# R121.net
KiCad netlist of a schematic drawn in EAGLE
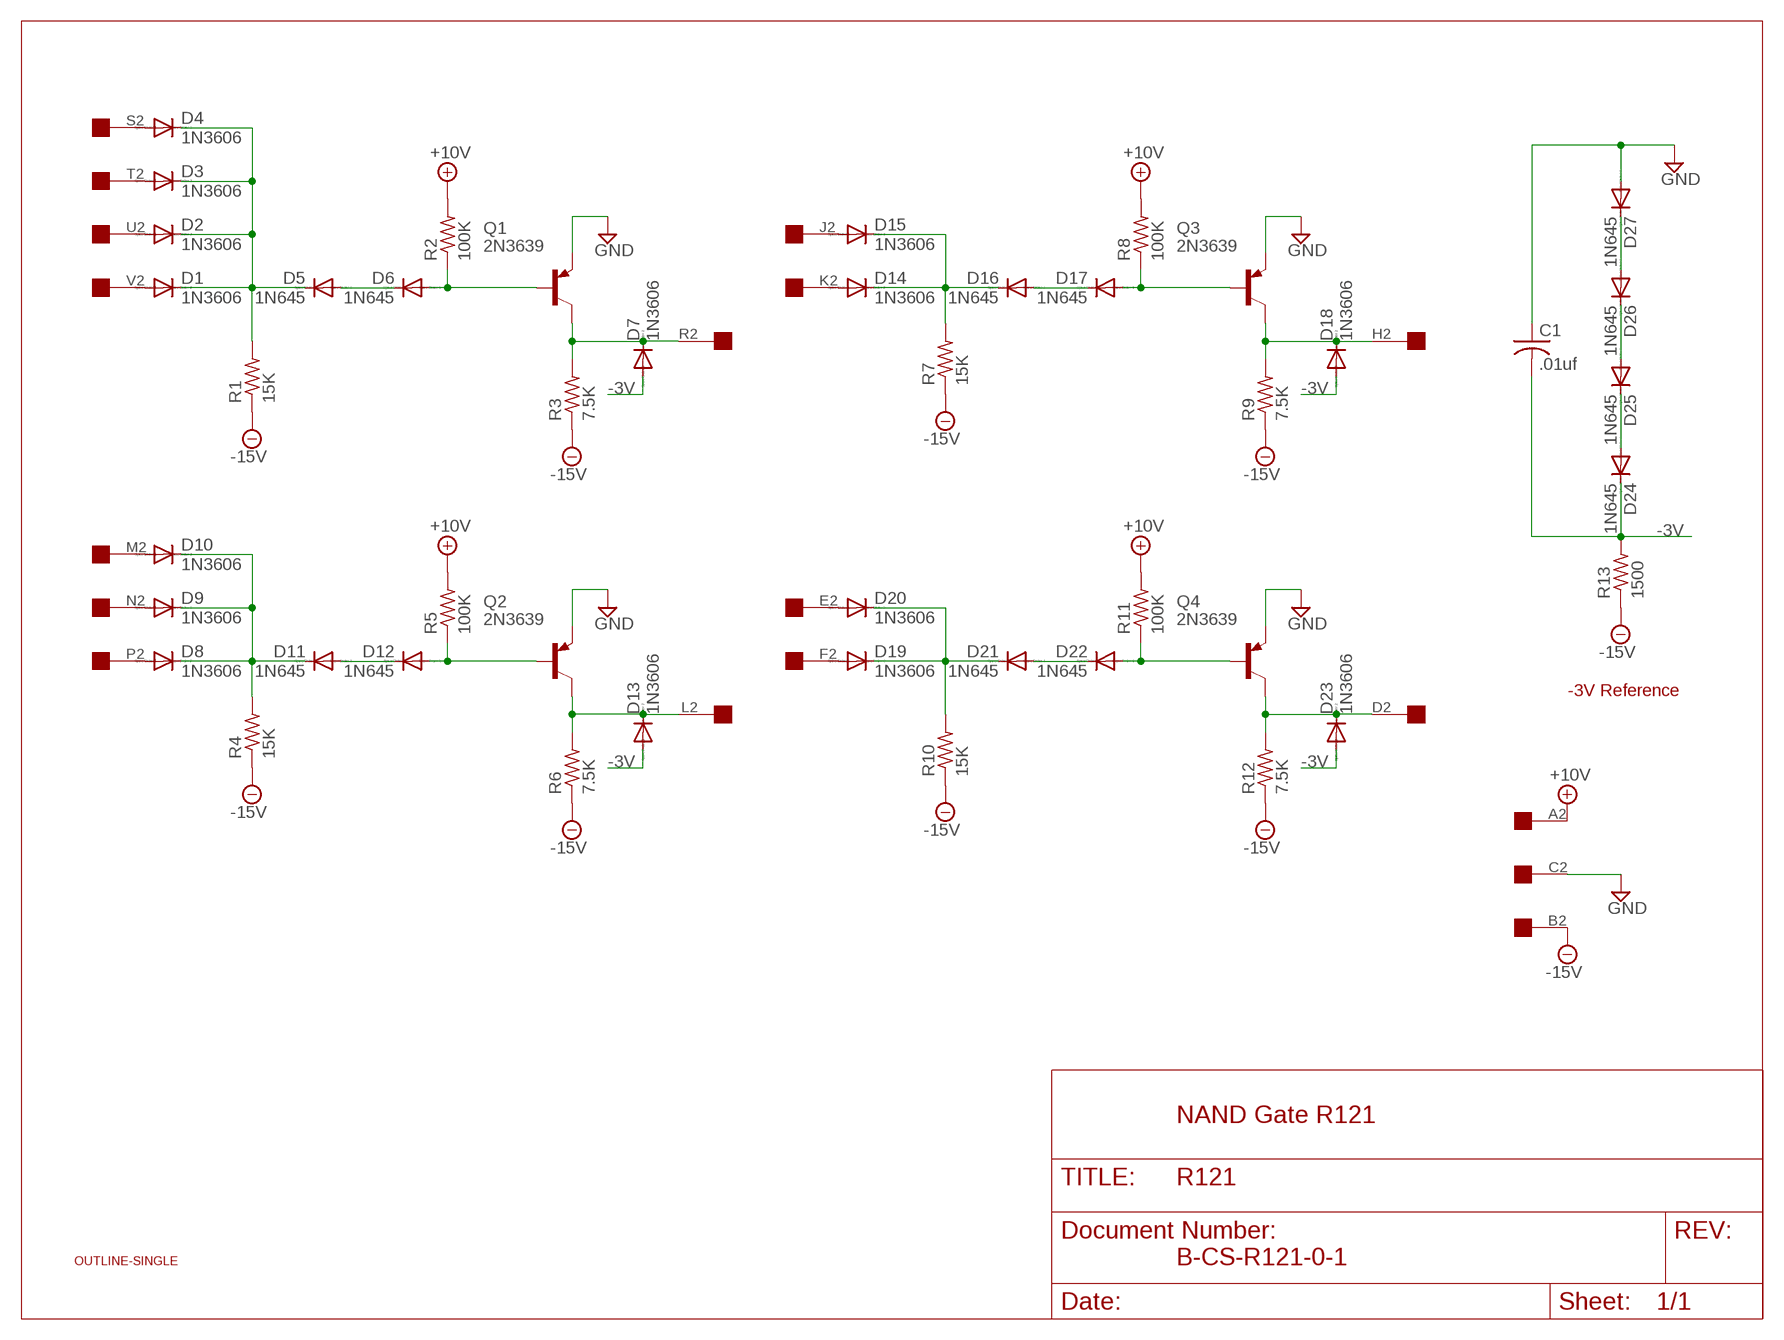
[diagram p0: schematic, sheet 1]

(export (version "E")
  (design (tool "Eeschema 10.0.6"))
  (components
    (comp (ref "C1")
      (value ".01uf")
      (footprint "eagle-import:C050-025X075")
      (libsource (lib "eagle-import") (part "C-US050-025X075"))
    )
    (comp (ref "D1")
      (value "1N3606")
      (footprint "eagle-import:DO35-10")
      (libsource (lib "eagle-import") (part "1N4148DO35-10"))
    )
    (comp (ref "D2")
      (value "1N3606")
      (footprint "eagle-import:DO35-10")
      (libsource (lib "eagle-import") (part "1N4148DO35-10"))
    )
    (comp (ref "D3")
      (value "1N3606")
      (footprint "eagle-import:DO35-10")
      (libsource (lib "eagle-import") (part "1N4148DO35-10"))
    )
    (comp (ref "D4")
      (value "1N3606")
      (footprint "eagle-import:DO35-10")
      (libsource (lib "eagle-import") (part "1N4148DO35-10"))
    )
    (comp (ref "D5")
      (value "1N645")
      (footprint "eagle-import:DO35-10")
      (libsource (lib "eagle-import") (part "1N4148DO35-10"))
    )
    (comp (ref "D6")
      (value "1N645")
      (footprint "eagle-import:DO35-10")
      (libsource (lib "eagle-import") (part "1N4148DO35-10"))
    )
    (comp (ref "D7")
      (value "1N3606")
      (footprint "eagle-import:DO35-10")
      (libsource (lib "eagle-import") (part "1N4148DO35-10"))
    )
    (comp (ref "D8")
      (value "1N3606")
      (footprint "eagle-import:DO35-10")
      (libsource (lib "eagle-import") (part "1N4148DO35-10"))
    )
    (comp (ref "D9")
      (value "1N3606")
      (footprint "eagle-import:DO35-10")
      (libsource (lib "eagle-import") (part "1N4148DO35-10"))
    )
    (comp (ref "D10")
      (value "1N3606")
      (footprint "eagle-import:DO35-10")
      (libsource (lib "eagle-import") (part "1N4148DO35-10"))
    )
    (comp (ref "D11")
      (value "1N645")
      (footprint "eagle-import:DO35-10")
      (libsource (lib "eagle-import") (part "1N4148DO35-10"))
    )
    (comp (ref "D12")
      (value "1N645")
      (footprint "eagle-import:DO35-10")
      (libsource (lib "eagle-import") (part "1N4148DO35-10"))
    )
    (comp (ref "D13")
      (value "1N3606")
      (footprint "eagle-import:DO35-10")
      (libsource (lib "eagle-import") (part "1N4148DO35-10"))
    )
    (comp (ref "D14")
      (value "1N3606")
      (footprint "eagle-import:DO35-10")
      (libsource (lib "eagle-import") (part "1N4148DO35-10"))
    )
    (comp (ref "D15")
      (value "1N3606")
      (footprint "eagle-import:DO35-10")
      (libsource (lib "eagle-import") (part "1N4148DO35-10"))
    )
    (comp (ref "D16")
      (value "1N645")
      (footprint "eagle-import:DO35-10")
      (libsource (lib "eagle-import") (part "1N4148DO35-10"))
    )
    (comp (ref "D17")
      (value "1N645")
      (footprint "eagle-import:DO35-10")
      (libsource (lib "eagle-import") (part "1N4148DO35-10"))
    )
    (comp (ref "D18")
      (value "1N3606")
      (footprint "eagle-import:DO35-10")
      (libsource (lib "eagle-import") (part "1N4148DO35-10"))
    )
    (comp (ref "D19")
      (value "1N3606")
      (footprint "eagle-import:DO35-10")
      (libsource (lib "eagle-import") (part "1N4148DO35-10"))
    )
    (comp (ref "D20")
      (value "1N3606")
      (footprint "eagle-import:DO35-10")
      (libsource (lib "eagle-import") (part "1N4148DO35-10"))
    )
    (comp (ref "D21")
      (value "1N645")
      (footprint "eagle-import:DO35-10")
      (libsource (lib "eagle-import") (part "1N4148DO35-10"))
    )
    (comp (ref "D22")
      (value "1N645")
      (footprint "eagle-import:DO35-10")
      (libsource (lib "eagle-import") (part "1N4148DO35-10"))
    )
    (comp (ref "D23")
      (value "1N3606")
      (footprint "eagle-import:DO35-10")
      (libsource (lib "eagle-import") (part "1N4148DO35-10"))
    )
    (comp (ref "D24")
      (value "1N645")
      (footprint "eagle-import:DO35-10")
      (libsource (lib "eagle-import") (part "1N4148DO35-10"))
    )
    (comp (ref "D25")
      (value "1N645")
      (footprint "eagle-import:DO35-10")
      (libsource (lib "eagle-import") (part "1N4148DO35-10"))
    )
    (comp (ref "D26")
      (value "1N645")
      (footprint "eagle-import:DO35-10")
      (libsource (lib "eagle-import") (part "1N4148DO35-10"))
    )
    (comp (ref "D27")
      (value "1N645")
      (footprint "eagle-import:DO35-10")
      (libsource (lib "eagle-import") (part "1N4148DO35-10"))
    )
    (comp (ref "Q1")
      (value "2N3639")
      (footprint "eagle-import:TO39")
      (libsource (lib "eagle-import") (part "2N3637"))
    )
    (comp (ref "Q2")
      (value "2N3639")
      (footprint "eagle-import:TO39")
      (libsource (lib "eagle-import") (part "2N3637"))
    )
    (comp (ref "Q3")
      (value "2N3639")
      (footprint "eagle-import:TO39")
      (libsource (lib "eagle-import") (part "2N3637"))
    )
    (comp (ref "Q4")
      (value "2N3639")
      (footprint "eagle-import:TO39")
      (libsource (lib "eagle-import") (part "2N3637"))
    )
    (comp (ref "R1")
      (value "15K")
      (footprint "eagle-import:0207_10")
      (libsource (lib "eagle-import") (part "R-US_0207/10"))
    )
    (comp (ref "R2")
      (value "100K")
      (footprint "eagle-import:0207_10")
      (libsource (lib "eagle-import") (part "R-US_0207/10"))
    )
    (comp (ref "R3")
      (value "7.5K")
      (footprint "eagle-import:0207_10")
      (libsource (lib "eagle-import") (part "R-US_0207/10"))
    )
    (comp (ref "R4")
      (value "15K")
      (footprint "eagle-import:0207_10")
      (libsource (lib "eagle-import") (part "R-US_0207/10"))
    )
    (comp (ref "R5")
      (value "100K")
      (footprint "eagle-import:0207_10")
      (libsource (lib "eagle-import") (part "R-US_0207/10"))
    )
    (comp (ref "R6")
      (value "7.5K")
      (footprint "eagle-import:0207_10")
      (libsource (lib "eagle-import") (part "R-US_0207/10"))
    )
    (comp (ref "R7")
      (value "15K")
      (footprint "eagle-import:0207_10")
      (libsource (lib "eagle-import") (part "R-US_0207/10"))
    )
    (comp (ref "R8")
      (value "100K")
      (footprint "eagle-import:0207_10")
      (libsource (lib "eagle-import") (part "R-US_0207/10"))
    )
    (comp (ref "R9")
      (value "7.5K")
      (footprint "eagle-import:0207_10")
      (libsource (lib "eagle-import") (part "R-US_0207/10"))
    )
    (comp (ref "R10")
      (value "15K")
      (footprint "eagle-import:0207_10")
      (libsource (lib "eagle-import") (part "R-US_0207/10"))
    )
    (comp (ref "R11")
      (value "100K")
      (footprint "eagle-import:0207_10")
      (libsource (lib "eagle-import") (part "R-US_0207/10"))
    )
    (comp (ref "R12")
      (value "7.5K")
      (footprint "eagle-import:0207_10")
      (libsource (lib "eagle-import") (part "R-US_0207/10"))
    )
    (comp (ref "R13")
      (value "1500")
      (footprint "eagle-import:0207_10")
      (libsource (lib "eagle-import") (part "R-US_0207/10"))
    )
    (comp (ref "U$1")
      (value "OUTLINE-SINGLE")
      (footprint "eagle-import:SINGLE")
      (libsource (lib "eagle-import") (part "OUTLINE-SINGLE"))
    )
    (comp (ref "U$2")
      (value "EDGE-1")
      (footprint "eagle-import:EDGE-CON1")
      (libsource (lib "eagle-import") (part "EDGE-1"))
    )
  )
  (nets
    (net (code "1") (name "+10V") (class "Default")
      (node (ref "R11") (pin "2") (pinfunction "2_2") (pintype "passive"))
      (node (ref "R2") (pin "2") (pinfunction "2_2") (pintype "passive"))
      (node (ref "R5") (pin "2") (pinfunction "2_2") (pintype "passive"))
      (node (ref "R8") (pin "2") (pinfunction "2_2") (pintype "passive"))
      (node (ref "U$2") (pin "A2") (pinfunction "1_A2") (pintype "bidirectional"))
    )
    (net (code "2") (name "-15V") (class "Default")
      (node (ref "R1") (pin "1") (pinfunction "1_1") (pintype "passive"))
      (node (ref "R10") (pin "1") (pinfunction "1_1") (pintype "passive"))
      (node (ref "R12") (pin "1") (pinfunction "1_1") (pintype "passive"))
      (node (ref "R13") (pin "1") (pinfunction "1_1") (pintype "passive"))
      (node (ref "R3") (pin "1") (pinfunction "1_1") (pintype "passive"))
      (node (ref "R4") (pin "1") (pinfunction "1_1") (pintype "passive"))
      (node (ref "R6") (pin "1") (pinfunction "1_1") (pintype "passive"))
      (node (ref "R7") (pin "1") (pinfunction "1_1") (pintype "passive"))
      (node (ref "R9") (pin "1") (pinfunction "1_1") (pintype "passive"))
      (node (ref "U$2") (pin "B2") (pinfunction "1_B2") (pintype "bidirectional"))
    )
    (net (code "3") (name "/-3V") (class "Default")
      (node (ref "C1") (pin "2") (pinfunction "2_2") (pintype "passive"))
      (node (ref "D13") (pin "A") (pinfunction "A_A") (pintype "passive"))
      (node (ref "D18") (pin "A") (pinfunction "A_A") (pintype "passive"))
      (node (ref "D23") (pin "A") (pinfunction "A_A") (pintype "passive"))
      (node (ref "D24") (pin "C") (pinfunction "C_C") (pintype "passive"))
      (node (ref "D7") (pin "A") (pinfunction "A_A") (pintype "passive"))
      (node (ref "R13") (pin "2") (pinfunction "2_2") (pintype "passive"))
    )
    (net (code "4") (name "GND") (class "Default")
      (node (ref "C1") (pin "1") (pinfunction "1_1") (pintype "passive"))
      (node (ref "D27") (pin "A") (pinfunction "A_A") (pintype "passive"))
      (node (ref "Q1") (pin "1") (pinfunction "E_1") (pintype "passive"))
      (node (ref "Q2") (pin "1") (pinfunction "E_1") (pintype "passive"))
      (node (ref "Q3") (pin "1") (pinfunction "E_1") (pintype "passive"))
      (node (ref "Q4") (pin "1") (pinfunction "E_1") (pintype "passive"))
      (node (ref "U$2") (pin "C2") (pinfunction "1_C2") (pintype "bidirectional"))
    )
    (net (code "5") (name "Net-(D1-PadC)") (class "Default")
      (node (ref "D1") (pin "C") (pinfunction "C_C") (pintype "passive"))
      (node (ref "D2") (pin "C") (pinfunction "C_C") (pintype "passive"))
      (node (ref "D3") (pin "C") (pinfunction "C_C") (pintype "passive"))
      (node (ref "D4") (pin "C") (pinfunction "C_C") (pintype "passive"))
      (node (ref "D5") (pin "C") (pinfunction "C_C") (pintype "passive"))
      (node (ref "R1") (pin "2") (pinfunction "2_2") (pintype "passive"))
    )
    (net (code "6") (name "Net-(D5-PadA)") (class "Default")
      (node (ref "D5") (pin "A") (pinfunction "A_A") (pintype "passive"))
      (node (ref "D6") (pin "C") (pinfunction "C_C") (pintype "passive"))
    )
    (net (code "7") (name "Net-(D10-PadC)") (class "Default")
      (node (ref "D10") (pin "C") (pinfunction "C_C") (pintype "passive"))
      (node (ref "D11") (pin "C") (pinfunction "C_C") (pintype "passive"))
      (node (ref "D8") (pin "C") (pinfunction "C_C") (pintype "passive"))
      (node (ref "D9") (pin "C") (pinfunction "C_C") (pintype "passive"))
      (node (ref "R4") (pin "2") (pinfunction "2_2") (pintype "passive"))
    )
    (net (code "8") (name "Net-(D11-PadA)") (class "Default")
      (node (ref "D11") (pin "A") (pinfunction "A_A") (pintype "passive"))
      (node (ref "D12") (pin "C") (pinfunction "C_C") (pintype "passive"))
    )
    (net (code "9") (name "Net-(D14-PadC)") (class "Default")
      (node (ref "D14") (pin "C") (pinfunction "C_C") (pintype "passive"))
      (node (ref "D15") (pin "C") (pinfunction "C_C") (pintype "passive"))
      (node (ref "D16") (pin "C") (pinfunction "C_C") (pintype "passive"))
      (node (ref "R7") (pin "2") (pinfunction "2_2") (pintype "passive"))
    )
    (net (code "10") (name "Net-(D16-PadA)") (class "Default")
      (node (ref "D16") (pin "A") (pinfunction "A_A") (pintype "passive"))
      (node (ref "D17") (pin "C") (pinfunction "C_C") (pintype "passive"))
    )
    (net (code "11") (name "Net-(D19-PadC)") (class "Default")
      (node (ref "D19") (pin "C") (pinfunction "C_C") (pintype "passive"))
      (node (ref "D20") (pin "C") (pinfunction "C_C") (pintype "passive"))
      (node (ref "D21") (pin "C") (pinfunction "C_C") (pintype "passive"))
      (node (ref "R10") (pin "2") (pinfunction "2_2") (pintype "passive"))
    )
    (net (code "12") (name "Net-(D21-PadA)") (class "Default")
      (node (ref "D21") (pin "A") (pinfunction "A_A") (pintype "passive"))
      (node (ref "D22") (pin "C") (pinfunction "C_C") (pintype "passive"))
    )
    (net (code "13") (name "Net-(D24-PadA)") (class "Default")
      (node (ref "D24") (pin "A") (pinfunction "A_A") (pintype "passive"))
      (node (ref "D25") (pin "C") (pinfunction "C_C") (pintype "passive"))
    )
    (net (code "14") (name "Net-(D25-PadA)") (class "Default")
      (node (ref "D25") (pin "A") (pinfunction "A_A") (pintype "passive"))
      (node (ref "D26") (pin "C") (pinfunction "C_C") (pintype "passive"))
    )
    (net (code "15") (name "Net-(D26-PadA)") (class "Default")
      (node (ref "D26") (pin "A") (pinfunction "A_A") (pintype "passive"))
      (node (ref "D27") (pin "C") (pinfunction "C_C") (pintype "passive"))
    )
    (net (code "16") (name "Net-(Q1-B)") (class "Default")
      (node (ref "D6") (pin "A") (pinfunction "A_A") (pintype "passive"))
      (node (ref "Q1") (pin "2") (pinfunction "B_2") (pintype "passive"))
      (node (ref "R2") (pin "1") (pinfunction "1_1") (pintype "passive"))
    )
    (net (code "17") (name "Net-(Q1-C)") (class "Default")
      (node (ref "D7") (pin "C") (pinfunction "C_C") (pintype "passive"))
      (node (ref "Q1") (pin "3") (pinfunction "C_3") (pintype "passive"))
      (node (ref "R3") (pin "2") (pinfunction "2_2") (pintype "passive"))
      (node (ref "U$2") (pin "R2") (pinfunction "1_R2") (pintype "bidirectional"))
    )
    (net (code "18") (name "Net-(Q2-B)") (class "Default")
      (node (ref "D12") (pin "A") (pinfunction "A_A") (pintype "passive"))
      (node (ref "Q2") (pin "2") (pinfunction "B_2") (pintype "passive"))
      (node (ref "R5") (pin "1") (pinfunction "1_1") (pintype "passive"))
    )
    (net (code "19") (name "Net-(Q2-C)") (class "Default")
      (node (ref "D13") (pin "C") (pinfunction "C_C") (pintype "passive"))
      (node (ref "Q2") (pin "3") (pinfunction "C_3") (pintype "passive"))
      (node (ref "R6") (pin "2") (pinfunction "2_2") (pintype "passive"))
      (node (ref "U$2") (pin "L2") (pinfunction "1_L2") (pintype "bidirectional"))
    )
    (net (code "20") (name "Net-(Q3-B)") (class "Default")
      (node (ref "D17") (pin "A") (pinfunction "A_A") (pintype "passive"))
      (node (ref "Q3") (pin "2") (pinfunction "B_2") (pintype "passive"))
      (node (ref "R8") (pin "1") (pinfunction "1_1") (pintype "passive"))
    )
    (net (code "21") (name "Net-(Q3-C)") (class "Default")
      (node (ref "D18") (pin "C") (pinfunction "C_C") (pintype "passive"))
      (node (ref "Q3") (pin "3") (pinfunction "C_3") (pintype "passive"))
      (node (ref "R9") (pin "2") (pinfunction "2_2") (pintype "passive"))
      (node (ref "U$2") (pin "H2") (pinfunction "1_H2") (pintype "bidirectional"))
    )
    (net (code "22") (name "Net-(Q4-B)") (class "Default")
      (node (ref "D22") (pin "A") (pinfunction "A_A") (pintype "passive"))
      (node (ref "Q4") (pin "2") (pinfunction "B_2") (pintype "passive"))
      (node (ref "R11") (pin "1") (pinfunction "1_1") (pintype "passive"))
    )
    (net (code "23") (name "Net-(Q4-C)") (class "Default")
      (node (ref "D23") (pin "C") (pinfunction "C_C") (pintype "passive"))
      (node (ref "Q4") (pin "3") (pinfunction "C_3") (pintype "passive"))
      (node (ref "R12") (pin "2") (pinfunction "2_2") (pintype "passive"))
      (node (ref "U$2") (pin "D2") (pinfunction "1_D2") (pintype "bidirectional"))
    )
    (net (code "24") (name "Net-(U$2E-1)") (class "Default")
      (node (ref "D20") (pin "A") (pinfunction "A_A") (pintype "passive"))
      (node (ref "U$2") (pin "E2") (pinfunction "1_E2") (pintype "bidirectional"))
    )
    (net (code "25") (name "Net-(U$2F-1)") (class "Default")
      (node (ref "D19") (pin "A") (pinfunction "A_A") (pintype "passive"))
      (node (ref "U$2") (pin "F2") (pinfunction "1_F2") (pintype "bidirectional"))
    )
    (net (code "26") (name "Net-(U$2H-1)") (class "Default")
      (node (ref "D15") (pin "A") (pinfunction "A_A") (pintype "passive"))
      (node (ref "U$2") (pin "J2") (pinfunction "1_J2") (pintype "bidirectional"))
    )
    (net (code "27") (name "Net-(U$2I-1)") (class "Default")
      (node (ref "D14") (pin "A") (pinfunction "A_A") (pintype "passive"))
      (node (ref "U$2") (pin "K2") (pinfunction "1_K2") (pintype "bidirectional"))
    )
    (net (code "28") (name "Net-(U$2K-1)") (class "Default")
      (node (ref "D10") (pin "A") (pinfunction "A_A") (pintype "passive"))
      (node (ref "U$2") (pin "M2") (pinfunction "1_M2") (pintype "bidirectional"))
    )
    (net (code "29") (name "Net-(U$2L-1)") (class "Default")
      (node (ref "D9") (pin "A") (pinfunction "A_A") (pintype "passive"))
      (node (ref "U$2") (pin "N2") (pinfunction "1_N2") (pintype "bidirectional"))
    )
    (net (code "30") (name "Net-(U$2M-1)") (class "Default")
      (node (ref "D8") (pin "A") (pinfunction "A_A") (pintype "passive"))
      (node (ref "U$2") (pin "P2") (pinfunction "1_P2") (pintype "bidirectional"))
    )
    (net (code "31") (name "Net-(U$2O-1)") (class "Default")
      (node (ref "D4") (pin "A") (pinfunction "A_A") (pintype "passive"))
      (node (ref "U$2") (pin "S2") (pinfunction "1_S2") (pintype "bidirectional"))
    )
    (net (code "32") (name "Net-(U$2P-1)") (class "Default")
      (node (ref "D3") (pin "A") (pinfunction "A_A") (pintype "passive"))
      (node (ref "U$2") (pin "T2") (pinfunction "1_T2") (pintype "bidirectional"))
    )
    (net (code "33") (name "Net-(U$2Q-1)") (class "Default")
      (node (ref "D2") (pin "A") (pinfunction "A_A") (pintype "passive"))
      (node (ref "U$2") (pin "U2") (pinfunction "1_U2") (pintype "bidirectional"))
    )
    (net (code "34") (name "Net-(U$2R-1)") (class "Default")
      (node (ref "D1") (pin "A") (pinfunction "A_A") (pintype "passive"))
      (node (ref "U$2") (pin "V2") (pinfunction "1_V2") (pintype "bidirectional"))
    )
  )
)
